# Adafruit_Relay_FeatherWing.net
KiCad netlist of a schematic drawn in EAGLE
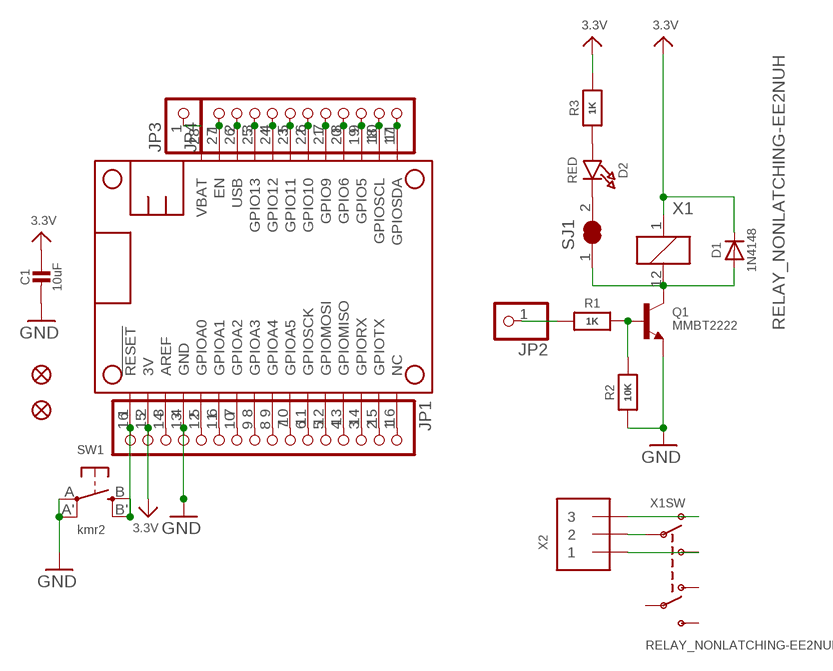
[diagram p0: schematic, sheet 1]

(export (version "E")
  (design (tool "Eeschema 10.0.6"))
  (components
    (comp (ref "C1")
      (value "10uF")
      (footprint "eagle-import:0805-NO")
      (libsource (lib "eagle-import") (part "CAP_CERAMIC0805-NOOUTLINE"))
    )
    (comp (ref "D1")
      (value "1N4148")
      (footprint "eagle-import:SOD-323")
      (libsource (lib "eagle-import") (part "DIODESOD-323"))
    )
    (comp (ref "D2")
      (value "RED")
      (footprint "eagle-import:CHIPLED_0805_NOOUTLINE")
      (libsource (lib "eagle-import") (part "LED0805_NOOUTLINE"))
    )
    (comp (ref "FID2")
      (value "FIDUCIAL\"\"")
      (footprint "eagle-import:FIDUCIAL_1MM")
      (libsource (lib "eagle-import") (part "FIDUCIAL{dblquote}{dblquote}"))
    )
    (comp (ref "FID3")
      (value "FIDUCIAL\"\"")
      (footprint "eagle-import:FIDUCIAL_1MM")
      (libsource (lib "eagle-import") (part "FIDUCIAL{dblquote}{dblquote}"))
    )
    (comp (ref "JP1")
      (value "HEADER-1X16ROUND")
      (footprint "eagle-import:1X16_ROUND")
      (libsource (lib "eagle-import") (part "HEADER-1X16ROUND"))
    )
    (comp (ref "JP2")
      (value "HEADER-1X1ROUND")
      (footprint "eagle-import:1X01_ROUND")
      (libsource (lib "eagle-import") (part "HEADER-1X1ROUND"))
    )
    (comp (ref "JP3")
      (value "HEADER-1X1ROUND")
      (footprint "eagle-import:1X01_ROUND")
      (libsource (lib "eagle-import") (part "HEADER-1X1ROUND"))
    )
    (comp (ref "JP4")
      (value "HEADER-1X11")
      (footprint "eagle-import:1X11_ROUND")
      (libsource (lib "eagle-import") (part "HEADER-1X11"))
    )
    (comp (ref "MS1")
      (value "MICROSHIELD")
      (footprint "eagle-import:MICROSHIELD")
      (libsource (lib "eagle-import") (part "MICROSHIELD"))
    )
    (comp (ref "Q1")
      (value "MMBT2222")
      (footprint "eagle-import:SOT23-R")
      (libsource (lib "eagle-import") (part "TRANSISTOR_NPN"))
    )
    (comp (ref "R1")
      (value "1K")
      (footprint "eagle-import:0805-NO")
      (libsource (lib "eagle-import") (part "RESISTOR0805_NOOUTLINE"))
    )
    (comp (ref "R2")
      (value "10K")
      (footprint "eagle-import:0805-NO")
      (libsource (lib "eagle-import") (part "RESISTOR0805_NOOUTLINE"))
    )
    (comp (ref "R3")
      (value "1K")
      (footprint "eagle-import:0805-NO")
      (libsource (lib "eagle-import") (part "RESISTOR0805_NOOUTLINE"))
    )
    (comp (ref "SJ1")
      (value "SOLDERJUMPER_CLOSED")
      (footprint "eagle-import:SOLDERJUMPER_CLOSEDWIRE")
      (libsource (lib "eagle-import") (part "SOLDERJUMPER_CLOSED"))
    )
    (comp (ref "SW1")
      (value "kmr2")
      (footprint "eagle-import:BTN_KMR2_4.6X2.8")
      (libsource (lib "eagle-import") (part "SWITCH_TACT_SMT4.6X2.8"))
    )
    (comp (ref "X1")
      (value "RELAY_NONLATCHING-EE2NUH")
      (footprint "eagle-import:RELAY_EE2_NOLATCH")
      (libsource (lib "eagle-import") (part "RELAY_NONLATCHING-EE2NUH"))
    )
    (comp (ref "X2")
      (value "TERMBLOCK_1X3")
      (footprint "eagle-import:TERMBLOCK_1X3-3.5MM")
      (libsource (lib "eagle-import") (part "TERMBLOCK_1X3"))
    )
  )
  (nets
    (net (code "1") (name "3.3V") (class "Default")
      (node (ref "C1") (pin "1") (pinfunction "1_1") (pintype "passive"))
      (node (ref "D1") (pin "C") (pinfunction "C_C") (pintype "passive"))
      (node (ref "JP1") (pin "15") (pinfunction "15_15") (pintype "passive"))
      (node (ref "MS1") (pin "2") (pinfunction "3V_2") (pintype "power_in"))
      (node (ref "R3") (pin "2") (pinfunction "2_2") (pintype "passive"))
      (node (ref "X1") (pin "1") (pinfunction "1_1") (pintype "passive"))
    )
    (net (code "2") (name "GND") (class "Default")
      (node (ref "C1") (pin "2") (pinfunction "2_2") (pintype "passive"))
      (node (ref "JP1") (pin "13") (pinfunction "13_13") (pintype "passive"))
      (node (ref "MS1") (pin "4") (pinfunction "GND_4") (pintype "power_in"))
      (node (ref "Q1") (pin "2") (pinfunction "E_2") (pintype "passive"))
      (node (ref "R2") (pin "1") (pinfunction "1_1") (pintype "passive"))
      (node (ref "SW1") (pin "A") (pinfunction "P_A") (pintype "passive"))
      (node (ref "SW1") (pin "A'") (pinfunction "P1_A'") (pintype "passive"))
    )
    (net (code "3") (name "Net-(D2-PadA)") (class "Default")
      (node (ref "D2") (pin "A") (pinfunction "A_A") (pintype "passive"))
      (node (ref "R3") (pin "1") (pinfunction "1_1") (pintype "passive"))
    )
    (net (code "4") (name "Net-(D2-PadC)") (class "Default")
      (node (ref "D2") (pin "C") (pinfunction "C_C") (pintype "passive"))
      (node (ref "SJ1") (pin "2") (pinfunction "2_2") (pintype "passive"))
    )
    (net (code "5") (name "Net-(JP2-Pad1)") (class "Default")
      (node (ref "JP2") (pin "1") (pinfunction "1_1") (pintype "passive"))
      (node (ref "R1") (pin "1") (pinfunction "1_1") (pintype "passive"))
    )
    (net (code "6") (name "Net-(MS1-AREF)") (class "Default")
      (node (ref "JP1") (pin "14") (pinfunction "14_14") (pintype "passive"))
      (node (ref "MS1") (pin "3") (pinfunction "AREF_3") (pintype "passive"))
    )
    (net (code "7") (name "Net-(MS1-EN)") (class "Default")
      (node (ref "JP4") (pin "1") (pinfunction "1_1") (pintype "passive"))
      (node (ref "MS1") (pin "27") (pinfunction "EN_27") (pintype "passive"))
    )
    (net (code "8") (name "Net-(MS1-GPIO5)") (class "Default")
      (node (ref "JP4") (pin "9") (pinfunction "9_9") (pintype "passive"))
      (node (ref "MS1") (pin "19") (pinfunction "GPIO5_19") (pintype "bidirectional"))
    )
    (net (code "9") (name "Net-(MS1-GPIO6)") (class "Default")
      (node (ref "JP4") (pin "8") (pinfunction "8_8") (pintype "passive"))
      (node (ref "MS1") (pin "20") (pinfunction "GPIO6_20") (pintype "bidirectional"))
    )
    (net (code "10") (name "Net-(MS1-GPIO9)") (class "Default")
      (node (ref "JP4") (pin "7") (pinfunction "7_7") (pintype "passive"))
      (node (ref "MS1") (pin "21") (pinfunction "GPIO9_21") (pintype "bidirectional"))
    )
    (net (code "11") (name "Net-(MS1-GPIO10)") (class "Default")
      (node (ref "JP4") (pin "6") (pinfunction "6_6") (pintype "passive"))
      (node (ref "MS1") (pin "22") (pinfunction "GPIO10_22") (pintype "bidirectional"))
    )
    (net (code "12") (name "Net-(MS1-GPIO11)") (class "Default")
      (node (ref "JP4") (pin "5") (pinfunction "5_5") (pintype "passive"))
      (node (ref "MS1") (pin "23") (pinfunction "GPIO11_23") (pintype "bidirectional"))
    )
    (net (code "13") (name "Net-(MS1-GPIO12)") (class "Default")
      (node (ref "JP4") (pin "4") (pinfunction "4_4") (pintype "passive"))
      (node (ref "MS1") (pin "24") (pinfunction "GPIO12_24") (pintype "bidirectional"))
    )
    (net (code "14") (name "Net-(MS1-GPIO13)") (class "Default")
      (node (ref "JP4") (pin "3") (pinfunction "3_3") (pintype "passive"))
      (node (ref "MS1") (pin "25") (pinfunction "GPIO13_25") (pintype "bidirectional"))
    )
    (net (code "15") (name "Net-(MS1-GPIOA0)") (class "Default")
      (node (ref "JP1") (pin "12") (pinfunction "12_12") (pintype "passive"))
      (node (ref "MS1") (pin "5") (pinfunction "GPIOA0_5") (pintype "bidirectional"))
    )
    (net (code "16") (name "Net-(MS1-GPIOA1)") (class "Default")
      (node (ref "JP1") (pin "11") (pinfunction "11_11") (pintype "passive"))
      (node (ref "MS1") (pin "6") (pinfunction "GPIOA1_6") (pintype "bidirectional"))
    )
    (net (code "17") (name "Net-(MS1-GPIOA2)") (class "Default")
      (node (ref "JP1") (pin "10") (pinfunction "10_10") (pintype "passive"))
      (node (ref "MS1") (pin "7") (pinfunction "GPIOA2_7") (pintype "bidirectional"))
    )
    (net (code "18") (name "Net-(MS1-GPIOA3)") (class "Default")
      (node (ref "JP1") (pin "9") (pinfunction "9_9") (pintype "passive"))
      (node (ref "MS1") (pin "8") (pinfunction "GPIOA3_8") (pintype "bidirectional"))
    )
    (net (code "19") (name "Net-(MS1-GPIOA4)") (class "Default")
      (node (ref "JP1") (pin "8") (pinfunction "8_8") (pintype "passive"))
      (node (ref "MS1") (pin "9") (pinfunction "GPIOA4_9") (pintype "bidirectional"))
    )
    (net (code "20") (name "Net-(MS1-GPIOA5)") (class "Default")
      (node (ref "JP1") (pin "7") (pinfunction "7_7") (pintype "passive"))
      (node (ref "MS1") (pin "10") (pinfunction "GPIOA5_10") (pintype "bidirectional"))
    )
    (net (code "21") (name "Net-(MS1-GPIOMISO)") (class "Default")
      (node (ref "JP1") (pin "4") (pinfunction "4_4") (pintype "passive"))
      (node (ref "MS1") (pin "13") (pinfunction "GPIOMISO_13") (pintype "bidirectional"))
    )
    (net (code "22") (name "Net-(MS1-GPIOMOSI)") (class "Default")
      (node (ref "JP1") (pin "5") (pinfunction "5_5") (pintype "passive"))
      (node (ref "MS1") (pin "12") (pinfunction "GPIOMOSI_12") (pintype "bidirectional"))
    )
    (net (code "23") (name "Net-(MS1-GPIORX)") (class "Default")
      (node (ref "JP1") (pin "3") (pinfunction "3_3") (pintype "passive"))
      (node (ref "MS1") (pin "14") (pinfunction "GPIORX_14") (pintype "bidirectional"))
    )
    (net (code "24") (name "Net-(MS1-GPIOSCK)") (class "Default")
      (node (ref "JP1") (pin "6") (pinfunction "6_6") (pintype "passive"))
      (node (ref "MS1") (pin "11") (pinfunction "GPIOSCK_11") (pintype "bidirectional"))
    )
    (net (code "25") (name "Net-(MS1-GPIOSCL)") (class "Default")
      (node (ref "JP4") (pin "10") (pinfunction "10_10") (pintype "passive"))
      (node (ref "MS1") (pin "18") (pinfunction "GPIOSCL_18") (pintype "bidirectional"))
    )
    (net (code "26") (name "Net-(MS1-GPIOSDA)") (class "Default")
      (node (ref "JP4") (pin "11") (pinfunction "11_11") (pintype "passive"))
      (node (ref "MS1") (pin "17") (pinfunction "GPIOSDA_17") (pintype "bidirectional"))
    )
    (net (code "27") (name "Net-(MS1-GPIOTX)") (class "Default")
      (node (ref "JP1") (pin "2") (pinfunction "2_2") (pintype "passive"))
      (node (ref "MS1") (pin "15") (pinfunction "GPIOTX_15") (pintype "bidirectional"))
    )
    (net (code "28") (name "Net-(MS1-NC)") (class "Default")
      (node (ref "JP1") (pin "1") (pinfunction "1_1") (pintype "passive"))
      (node (ref "MS1") (pin "16") (pinfunction "NC_16") (pintype "passive"))
    )
    (net (code "29") (name "Net-(MS1-USB)") (class "Default")
      (node (ref "JP4") (pin "2") (pinfunction "2_2") (pintype "passive"))
      (node (ref "MS1") (pin "26") (pinfunction "USB_26") (pintype "power_in"))
    )
    (net (code "30") (name "Net-(MS1-VBAT)") (class "Default")
      (node (ref "JP3") (pin "1") (pinfunction "1_1") (pintype "passive"))
      (node (ref "MS1") (pin "28") (pinfunction "VBAT_28") (pintype "power_in"))
    )
    (net (code "31") (name "Net-(MS1-~{RESET})") (class "Default")
      (node (ref "JP1") (pin "16") (pinfunction "16_16") (pintype "passive"))
      (node (ref "MS1") (pin "1") (pinfunction "~{RESET}_1") (pintype "input"))
      (node (ref "SW1") (pin "B") (pinfunction "S_B") (pintype "passive"))
      (node (ref "SW1") (pin "B'") (pinfunction "S1_B'") (pintype "passive"))
    )
    (net (code "32") (name "Net-(Q1-B)") (class "Default")
      (node (ref "Q1") (pin "1") (pinfunction "B_1") (pintype "passive"))
      (node (ref "R1") (pin "2") (pinfunction "2_2") (pintype "passive"))
      (node (ref "R2") (pin "2") (pinfunction "2_2") (pintype "passive"))
    )
    (net (code "33") (name "Net-(Q1-C)") (class "Default")
      (node (ref "D1") (pin "A") (pinfunction "A_A") (pintype "passive"))
      (node (ref "Q1") (pin "3") (pinfunction "C_3") (pintype "passive"))
      (node (ref "SJ1") (pin "1") (pinfunction "1_1") (pintype "passive"))
      (node (ref "X1") (pin "12") (pinfunction "2_12") (pintype "passive"))
    )
    (net (code "34") (name "Net-(X1B-O1)") (class "Default")
      (node (ref "X1") (pin "10") (pinfunction "O1_10") (pintype "passive"))
      (node (ref "X2") (pin "3") (pinfunction "3_3") (pintype "passive"))
    )
    (net (code "35") (name "Net-(X1B-P1)") (class "Default")
      (node (ref "X1") (pin "9") (pinfunction "P1_9") (pintype "passive"))
      (node (ref "X2") (pin "2") (pinfunction "2_2") (pintype "passive"))
    )
    (net (code "36") (name "Net-(X1B-S1)") (class "Default")
      (node (ref "X1") (pin "8") (pinfunction "S1_8") (pintype "passive"))
      (node (ref "X2") (pin "1") (pinfunction "1_1") (pintype "passive"))
    )
    (net (code "37") (name "unconnected-(X1B-O2-Pad3)") (class "Default")
      (node (ref "X1") (pin "3") (pinfunction "O2_3") (pintype "passive"))
    )
    (net (code "38") (name "unconnected-(X1B-P2-Pad4)") (class "Default")
      (node (ref "X1") (pin "4") (pinfunction "P2_4") (pintype "passive"))
    )
    (net (code "39") (name "unconnected-(X1B-S2-Pad5)") (class "Default")
      (node (ref "X1") (pin "5") (pinfunction "S2_5") (pintype "passive"))
    )
  )
)
